# LPC1768_2.net
KiCad netlist of a schematic drawn in Altium Designer
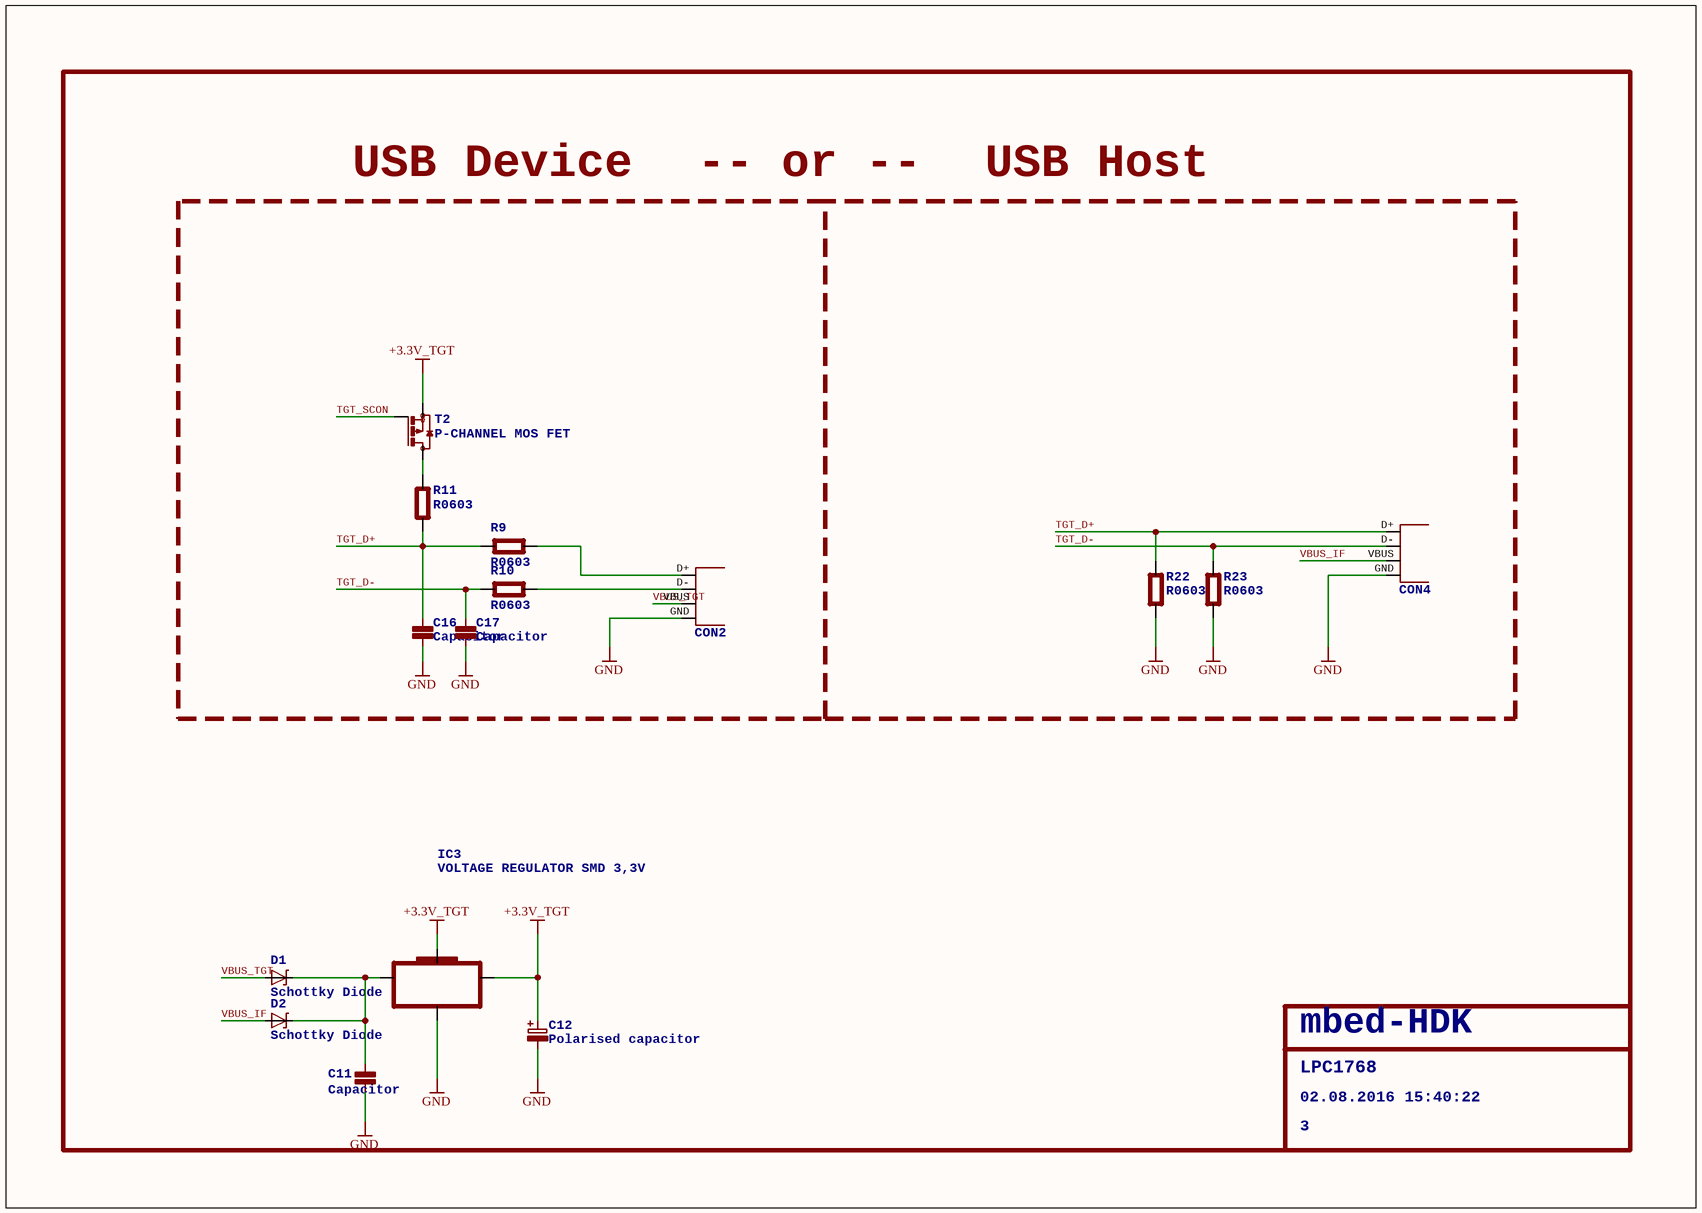
[diagram p0: LPC1768_2.SchDoc]

(export (version "E")
  (design (tool "Eeschema 10.0.6"))
  (components
    (comp (ref "C11") (value "Capacitor") (footprint "0603") (libsource (lib "mbed-HDK") (part "C0603")))
    (comp (ref "C12")
      (value "Polarised capacitor")
      (footprint "CASE-B")
      (libsource (lib "mbed-HDK") (part "C-POLB"))
    )
    (comp (ref "C16") (value "Capacitor") (footprint "0603") (libsource (lib "mbed-HDK") (part "C0603")))
    (comp (ref "C17") (value "Capacitor") (footprint "0603") (libsource (lib "mbed-HDK") (part "C0603")))
    (comp (ref "CON2")
      (value "USB Connectors")
      (footprint "USB-MB-S")
      (libsource (lib "mbed-HDK") (part "USB-MB-S"))
    )
    (comp (ref "CON4")
      (value "USB Connectors")
      (footprint "USB-A-H")
      (libsource (lib "mbed-HDK") (part "USB-A-H"))
    )
    (comp (ref "D1")
      (value "Schottky Diode")
      (footprint "BAT60A")
      (libsource (lib "mbed-HDK") (part "BAT60A"))
    )
    (comp (ref "D2")
      (value "Schottky Diode")
      (footprint "BAT60A")
      (libsource (lib "mbed-HDK") (part "BAT60A"))
    )
    (comp (ref "IC3")
      (value "VOLTAGE REGULATOR SMD 3,3V")
      (footprint "SOT223")
      (libsource (lib "mbed-HDK") (part "LD1117S33"))
    )
    (comp (ref "R9") (value "R0603") (footprint "0603") (libsource (lib "mbed-HDK") (part "R0603")))
    (comp (ref "R10") (value "R0603") (footprint "0603") (libsource (lib "mbed-HDK") (part "R0603")))
    (comp (ref "R11") (value "R0603") (footprint "0603") (libsource (lib "mbed-HDK") (part "R0603")))
    (comp (ref "R22") (value "R0603") (footprint "0603") (libsource (lib "mbed-HDK") (part "R0603")))
    (comp (ref "R23") (value "R0603") (footprint "0603") (libsource (lib "mbed-HDK") (part "R0603")))
    (comp (ref "T2")
      (value "P-CHANNEL MOS FET")
      (footprint "SOT23")
      (libsource (lib "mbed-HDK") (part "BSS84"))
    )
  )
  (nets
    (net (code "1") (name "+3.3V_TGT") (class "Default")
      (node (ref "C12") (pin "1") (pinfunction "1_1") (pintype "passive"))
      (node (ref "IC3") (pin "2") (pinfunction "OUT_2") (pintype "passive"))
      (node (ref "IC3") (pin "4") (pinfunction "K_4") (pintype "passive"))
      (node (ref "T2") (pin "2") (pinfunction "S_2") (pintype "passive"))
    )
    (net (code "2") (name "/TGT_D+") (class "Default")
      (node (ref "C16") (pin "1") (pinfunction "P$1_1") (pintype "passive"))
      (node (ref "CON4") (pin "D+") (pinfunction "D+_D+") (pintype "passive"))
      (node (ref "R11") (pin "2") (pinfunction "P$2_2") (pintype "passive"))
      (node (ref "R22") (pin "2") (pinfunction "P$2_2") (pintype "passive"))
      (node (ref "R9") (pin "1") (pinfunction "P$1_1") (pintype "passive"))
    )
    (net (code "3") (name "/TGT_D-") (class "Default")
      (node (ref "C17") (pin "1") (pinfunction "P$1_1") (pintype "passive"))
      (node (ref "CON4") (pin "D-") (pinfunction "D-_D-") (pintype "passive"))
      (node (ref "R10") (pin "1") (pinfunction "P$1_1") (pintype "passive"))
      (node (ref "R23") (pin "2") (pinfunction "P$2_2") (pintype "passive"))
    )
    (net (code "4") (name "/TGT_SCON") (class "Default")
      (node (ref "T2") (pin "1") (pinfunction "G_1") (pintype "passive"))
    )
    (net (code "5") (name "/VBUS_IF") (class "Default")
      (node (ref "CON4") (pin "VBUS") (pinfunction "VBUS_VBUS") (pintype "passive"))
      (node (ref "D2") (pin "A") (pinfunction "A_A") (pintype "passive"))
    )
    (net (code "6") (name "/VBUS_TGT") (class "Default")
      (node (ref "CON2") (pin "VBUS") (pinfunction "VBUS_VBUS") (pintype "passive"))
      (node (ref "D1") (pin "A") (pinfunction "A_A") (pintype "passive"))
    )
    (net (code "7") (name "GND") (class "Default")
      (node (ref "C11") (pin "2") (pinfunction "P$2_2") (pintype "passive"))
      (node (ref "C12") (pin "2") (pinfunction "2_2") (pintype "passive"))
      (node (ref "C16") (pin "2") (pinfunction "P$2_2") (pintype "passive"))
      (node (ref "C17") (pin "2") (pinfunction "P$2_2") (pintype "passive"))
      (node (ref "CON2") (pin "GND") (pinfunction "GND_GND") (pintype "passive"))
      (node (ref "CON4") (pin "GND") (pinfunction "GND_GND") (pintype "passive"))
      (node (ref "IC3") (pin "1") (pinfunction "GND_1") (pintype "passive"))
      (node (ref "R22") (pin "1") (pinfunction "P$1_1") (pintype "passive"))
      (node (ref "R23") (pin "1") (pinfunction "P$1_1") (pintype "passive"))
    )
    (net (code "8") (name "Net-(C11-P$1)") (class "Default")
      (node (ref "C11") (pin "1") (pinfunction "P$1_1") (pintype "passive"))
      (node (ref "D1") (pin "K") (pinfunction "K_K") (pintype "passive"))
      (node (ref "D2") (pin "K") (pinfunction "K_K") (pintype "passive"))
      (node (ref "IC3") (pin "3") (pinfunction "IN_3") (pintype "passive"))
    )
    (net (code "9") (name "Net-(R9-P$2)") (class "Default")
      (node (ref "CON2") (pin "D+") (pinfunction "D+_D+") (pintype "passive"))
      (node (ref "R9") (pin "2") (pinfunction "P$2_2") (pintype "passive"))
    )
    (net (code "10") (name "Net-(R10-P$2)") (class "Default")
      (node (ref "CON2") (pin "D-") (pinfunction "D-_D-") (pintype "passive"))
      (node (ref "R10") (pin "2") (pinfunction "P$2_2") (pintype "passive"))
    )
    (net (code "11") (name "Net-(R11-P$1)") (class "Default")
      (node (ref "R11") (pin "1") (pinfunction "P$1_1") (pintype "passive"))
      (node (ref "T2") (pin "3") (pinfunction "D_3") (pintype "passive"))
    )
  )
)
